# Adafruit_USB_Type_C_Downstream_Breakout_.net
KiCad netlist of a schematic drawn in EAGLE
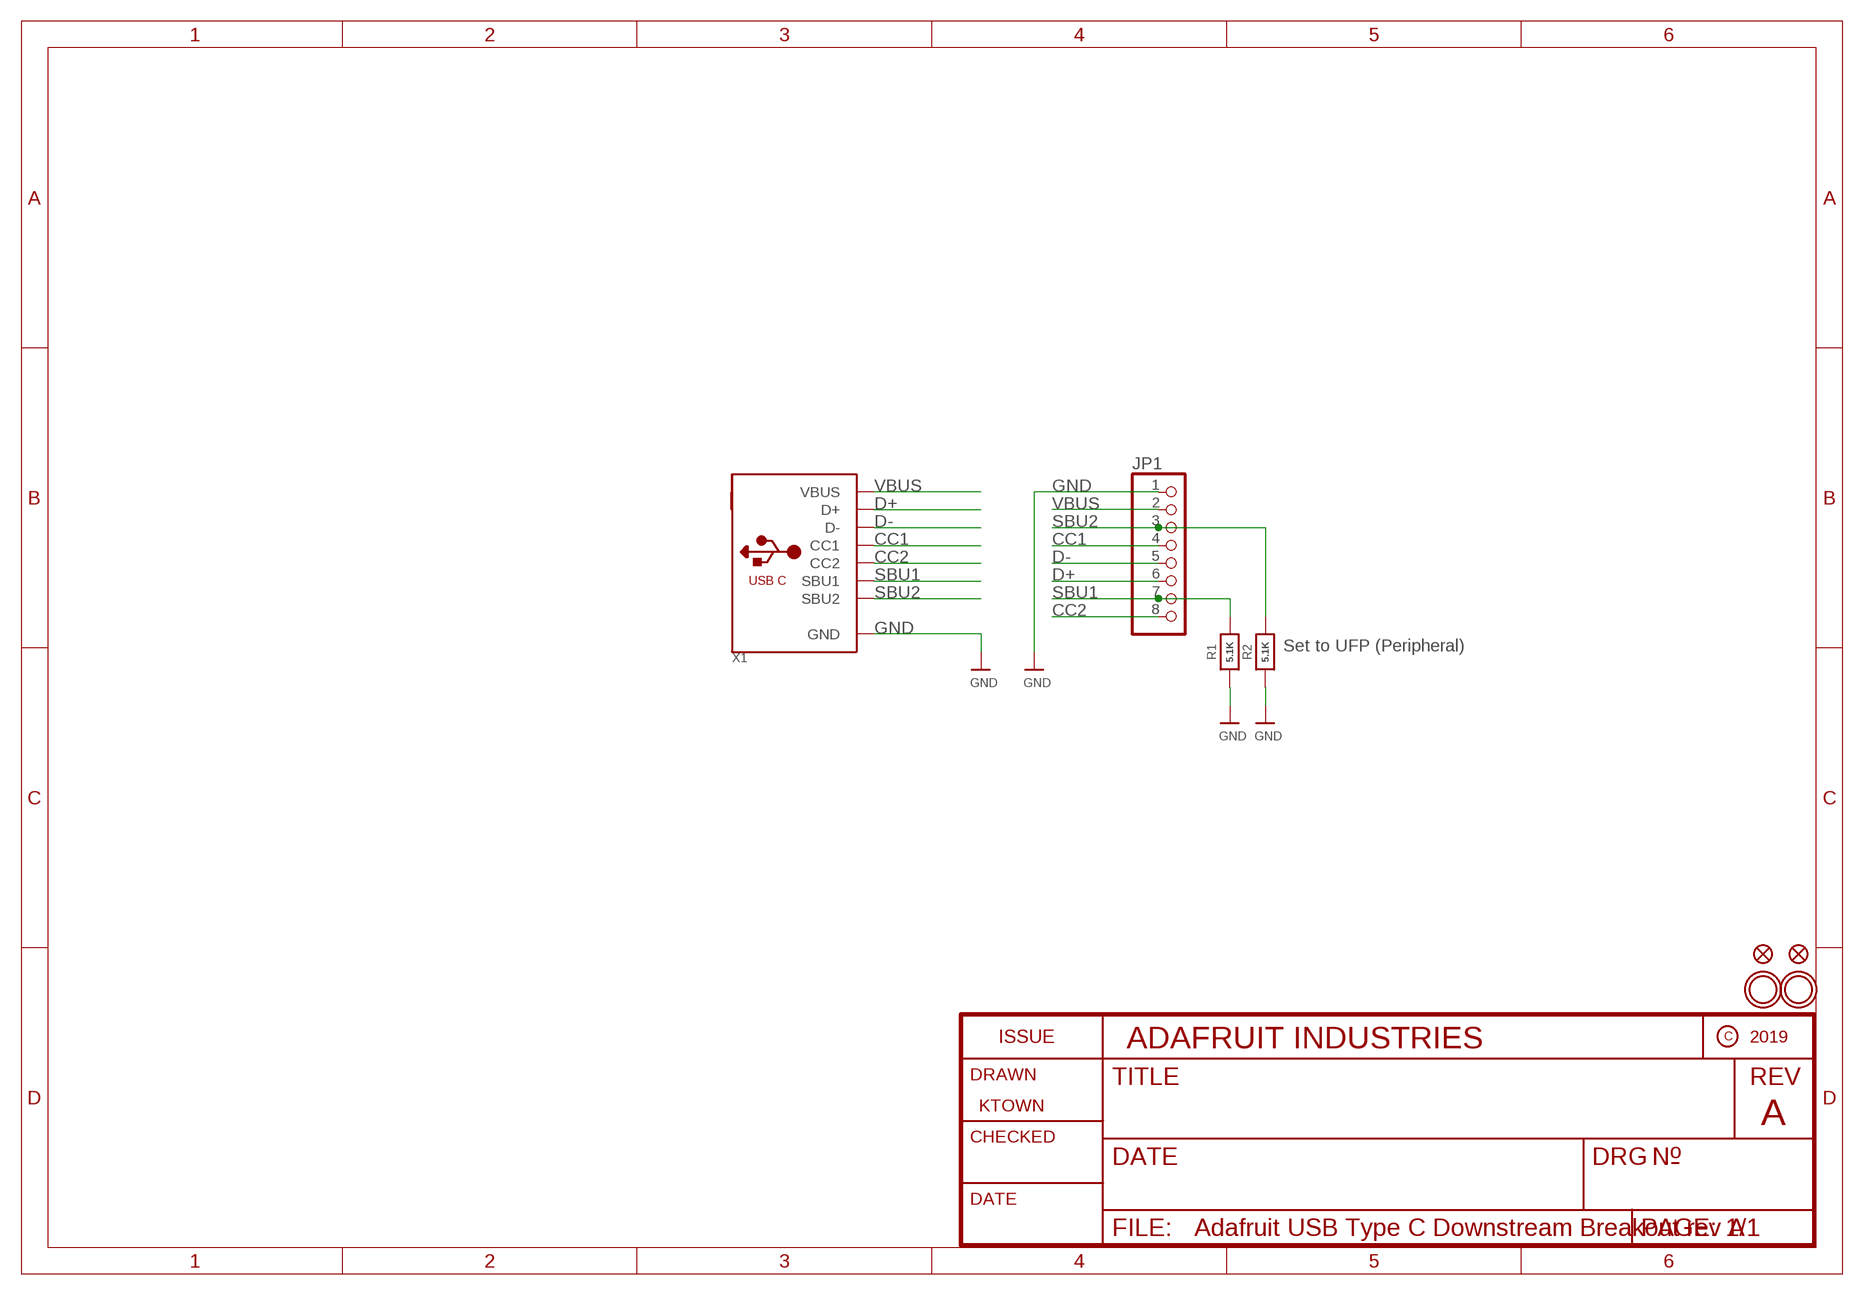
[diagram p0: schematic, sheet 1]

(export (version "E")
  (design (tool "Eeschema 10.0.6"))
  (components
    (comp (ref "FID1")
      (value "FIDUCIAL_1MM")
      (footprint "eagle-import:FIDUCIAL_1MM")
      (libsource (lib "eagle-import") (part "FIDUCIAL_1MM"))
    )
    (comp (ref "FID2")
      (value "FIDUCIAL_1MM")
      (footprint "eagle-import:FIDUCIAL_1MM")
      (libsource (lib "eagle-import") (part "FIDUCIAL_1MM"))
    )
    (comp (ref "JP1")
      (value "HEADER-1X876MIL")
      (footprint "eagle-import:1X08_ROUND_76")
      (libsource (lib "eagle-import") (part "HEADER-1X876MIL"))
    )
    (comp (ref "R1")
      (value "5.1K")
      (footprint "eagle-import:0603-NO")
      (libsource (lib "eagle-import") (part "RESISTOR_0603_NOOUT"))
    )
    (comp (ref "R2")
      (value "5.1K")
      (footprint "eagle-import:0603-NO")
      (libsource (lib "eagle-import") (part "RESISTOR_0603_NOOUT"))
    )
    (comp (ref "U$1")
      (value "MOUNTINGHOLE2.5")
      (footprint "eagle-import:MOUNTINGHOLE_2.5_PLATED")
      (libsource (lib "eagle-import") (part "MOUNTINGHOLE2.5"))
    )
    (comp (ref "U$2")
      (value "MOUNTINGHOLE2.5")
      (footprint "eagle-import:MOUNTINGHOLE_2.5_PLATED")
      (libsource (lib "eagle-import") (part "MOUNTINGHOLE2.5"))
    )
    (comp (ref "X1")
      (value "USB_C")
      (footprint "eagle-import:USB_C_CUSB31-CFM2AX-01-X")
      (libsource (lib "eagle-import") (part "USB_C"))
    )
  )
  (nets
    (net (code "1") (name "/CC1") (class "Default")
      (node (ref "JP1") (pin "4") (pinfunction "4_4") (pintype "passive"))
      (node (ref "X1") (pin "A5") (pinfunction "CC1_A5") (pintype "bidirectional"))
    )
    (net (code "2") (name "/CC2") (class "Default")
      (node (ref "JP1") (pin "8") (pinfunction "8_8") (pintype "passive"))
      (node (ref "X1") (pin "B5") (pinfunction "CC2_B5") (pintype "bidirectional"))
    )
    (net (code "3") (name "/D+") (class "Default")
      (node (ref "JP1") (pin "6") (pinfunction "6_6") (pintype "passive"))
      (node (ref "X1") (pin "A6") (pinfunction "D+_A6") (pintype "bidirectional"))
      (node (ref "X1") (pin "B6") (pinfunction "D+_B6") (pintype "bidirectional"))
    )
    (net (code "4") (name "/D-") (class "Default")
      (node (ref "JP1") (pin "5") (pinfunction "5_5") (pintype "passive"))
      (node (ref "X1") (pin "A7") (pinfunction "D-_A7") (pintype "bidirectional"))
      (node (ref "X1") (pin "B7") (pinfunction "D-_B7") (pintype "bidirectional"))
    )
    (net (code "5") (name "/SBU1") (class "Default")
      (node (ref "JP1") (pin "7") (pinfunction "7_7") (pintype "passive"))
      (node (ref "R1") (pin "2") (pinfunction "2_2") (pintype "passive"))
      (node (ref "X1") (pin "A8") (pinfunction "SBU1_A8") (pintype "bidirectional"))
    )
    (net (code "6") (name "/SBU2") (class "Default")
      (node (ref "JP1") (pin "3") (pinfunction "3_3") (pintype "passive"))
      (node (ref "R2") (pin "2") (pinfunction "2_2") (pintype "passive"))
      (node (ref "X1") (pin "B8") (pinfunction "SBU2_B8") (pintype "bidirectional"))
    )
    (net (code "7") (name "/VBUS") (class "Default")
      (node (ref "JP1") (pin "2") (pinfunction "2_2") (pintype "passive"))
      (node (ref "X1") (pin "A4B9") (pinfunction "VBUS_A4B9") (pintype "power_in"))
      (node (ref "X1") (pin "B4A9") (pinfunction "VBUS_B4A9") (pintype "power_in"))
    )
    (net (code "8") (name "GND") (class "Default")
      (node (ref "JP1") (pin "1") (pinfunction "1_1") (pintype "passive"))
      (node (ref "R1") (pin "1") (pinfunction "1_1") (pintype "passive"))
      (node (ref "R2") (pin "1") (pinfunction "1_1") (pintype "passive"))
      (node (ref "X1") (pin "A1B12") (pinfunction "GND_A1B12") (pintype "power_in"))
      (node (ref "X1") (pin "B1A12") (pinfunction "GND_B1A12") (pintype "power_in"))
    )
  )
)
